# gps_tracker.net
KiCad netlist of a schematic drawn in EAGLE
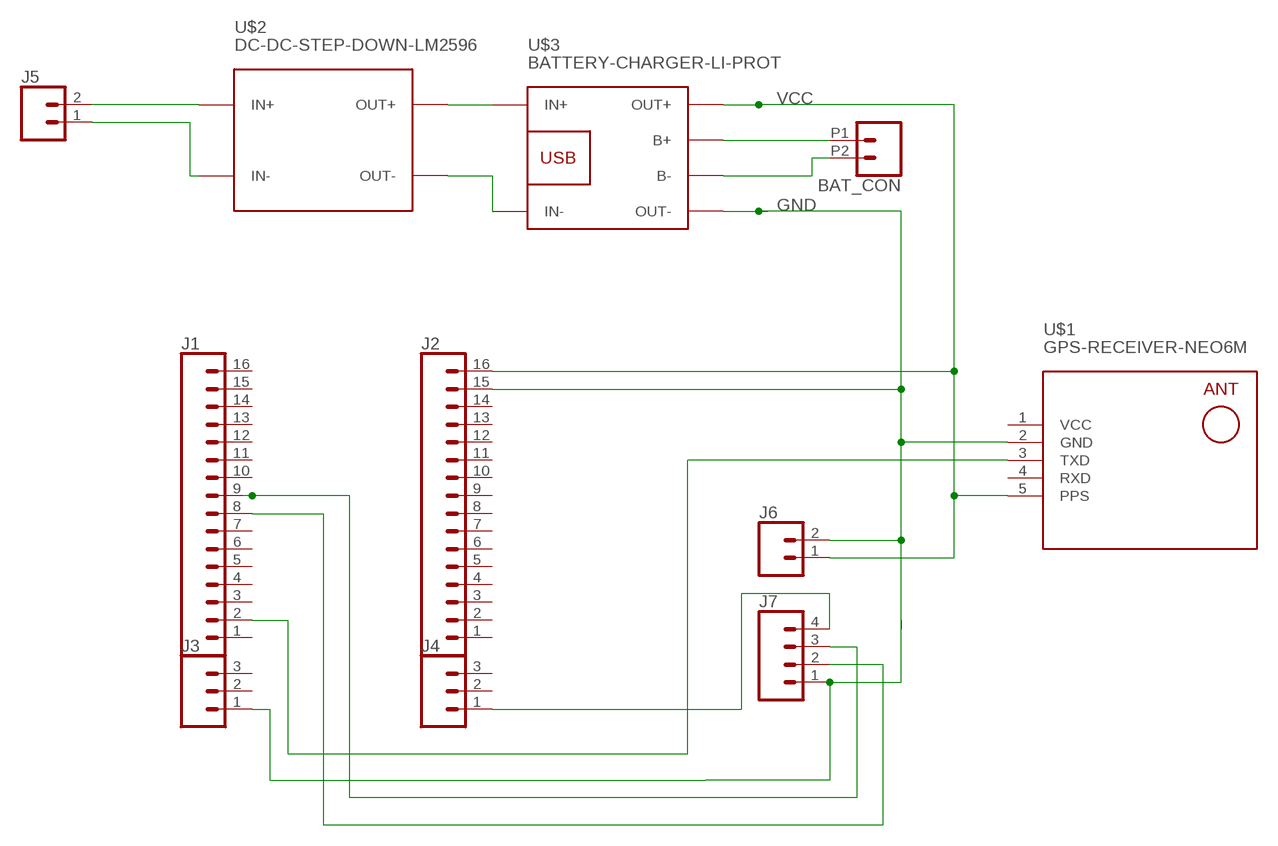
[diagram p0: schematic, sheet 1]

(export (version "E")
  (design (tool "Eeschema 10.0.6"))
  (components
    (comp (ref "BAT_CON")
      (value "CONN_022.54MM_SCREWTERM")
      (footprint "eagle-import:1X02_2.54_SCREWTERM")
      (libsource (lib "eagle-import") (part "CONN_022.54MM_SCREWTERM"))
    )
    (comp (ref "J1")
      (value "CONN_16LONGPADS")
      (footprint "eagle-import:1X16_LONGPADS")
      (fields (field (name "SPICEPREFIX") "X"))
      (libsource (lib "eagle-import") (part "CONN_16LONGPADS"))
    )
    (comp (ref "J2")
      (value "CONN_16LONGPADS")
      (footprint "eagle-import:1X16_LONGPADS")
      (fields (field (name "SPICEPREFIX") "X"))
      (libsource (lib "eagle-import") (part "CONN_16LONGPADS"))
    )
    (comp (ref "J3")
      (value "CONN_03LONGPADS")
      (footprint "eagle-import:1X03_LONGPADS")
      (fields (field (name "SPICEPREFIX") "J"))
      (libsource (lib "eagle-import") (part "CONN_03LONGPADS"))
    )
    (comp (ref "J4")
      (value "CONN_03LONGPADS")
      (footprint "eagle-import:1X03_LONGPADS")
      (fields (field (name "SPICEPREFIX") "J"))
      (libsource (lib "eagle-import") (part "CONN_03LONGPADS"))
    )
    (comp (ref "J5")
      (value "CONN_025MM")
      (footprint "eagle-import:SCREWTERMINAL-5MM-2")
      (libsource (lib "eagle-import") (part "CONN_025MM"))
    )
    (comp (ref "J6")
      (value "CONN_02PTH3")
      (footprint "eagle-import:1X02_LONGPADS")
      (libsource (lib "eagle-import") (part "CONN_02PTH3"))
    )
    (comp (ref "J7")
      (value "CONN_04LONGPADS")
      (footprint "eagle-import:1X04_LONGPADS")
      (libsource (lib "eagle-import") (part "CONN_04LONGPADS"))
    )
    (comp (ref "U$1")
      (value "GPS-RECEIVER-NEO6M")
      (footprint "eagle-import:GPS-RECEIVER-NEO6M")
      (libsource (lib "eagle-import") (part "GPS-RECEIVER-NEO6M"))
    )
    (comp (ref "U$2")
      (value "DC-DC-STEP-DOWN-LM2596")
      (footprint "eagle-import:DC-DC-STEP-DOWN-LM2596")
      (libsource (lib "eagle-import") (part "DC-DC-STEP-DOWN-LM2596"))
    )
    (comp (ref "U$3")
      (value "BATTERY-CHARGER-LI-PROT")
      (footprint "eagle-import:BATTERY-CHARGER-LI-PROT")
      (libsource (lib "eagle-import") (part "BATTERY-CHARGER-LI-PROT"))
    )
  )
  (nets
    (net (code "1") (name "/GND") (class "Default")
      (node (ref "J2") (pin "15") (pinfunction "15_15") (pintype "passive"))
      (node (ref "J3") (pin "1") (pinfunction "1_1") (pintype "passive"))
      (node (ref "J6") (pin "2") (pinfunction "2_2") (pintype "passive"))
      (node (ref "J7") (pin "1") (pinfunction "1_1") (pintype "passive"))
      (node (ref "U$1") (pin "2") (pinfunction "GND_2") (pintype "bidirectional"))
      (node (ref "U$3") (pin "OUT-") (pinfunction "OUT-_OUT-") (pintype "bidirectional"))
    )
    (net (code "2") (name "/RXD") (class "Default")
      (node (ref "U$1") (pin "4") (pinfunction "RXD_4") (pintype "power_in"))
    )
    (net (code "3") (name "/VCC") (class "Default")
      (node (ref "J2") (pin "16") (pinfunction "16_16") (pintype "passive"))
      (node (ref "J6") (pin "1") (pinfunction "1_1") (pintype "passive"))
      (node (ref "U$1") (pin "5") (pinfunction "PPS_5") (pintype "power_in"))
      (node (ref "U$3") (pin "OUT+") (pinfunction "OUT+_OUT+") (pintype "bidirectional"))
    )
    (net (code "4") (name "Net-(BAT_CON-1)") (class "Default")
      (node (ref "BAT_CON") (pin "P1") (pinfunction "1_P1") (pintype "passive"))
      (node (ref "U$3") (pin "B+") (pinfunction "B+_B+") (pintype "bidirectional"))
    )
    (net (code "5") (name "Net-(BAT_CON-2)") (class "Default")
      (node (ref "BAT_CON") (pin "P2") (pinfunction "2_P2") (pintype "passive"))
      (node (ref "U$3") (pin "B-") (pinfunction "B-_B-") (pintype "bidirectional"))
    )
    (net (code "6") (name "Net-(J1-Pad8)") (class "Default")
      (node (ref "J1") (pin "8") (pinfunction "8_8") (pintype "passive"))
      (node (ref "J7") (pin "2") (pinfunction "2_2") (pintype "passive"))
    )
    (net (code "7") (name "Net-(J1-Pad9)") (class "Default")
      (node (ref "J1") (pin "9") (pinfunction "9_9") (pintype "passive"))
      (node (ref "J7") (pin "3") (pinfunction "3_3") (pintype "passive"))
    )
    (net (code "8") (name "Net-(J4-Pad1)") (class "Default")
      (node (ref "J4") (pin "1") (pinfunction "1_1") (pintype "passive"))
      (node (ref "J7") (pin "4") (pinfunction "4_4") (pintype "passive"))
    )
    (net (code "9") (name "Net-(J5-Pad1)") (class "Default")
      (node (ref "J5") (pin "1") (pinfunction "1_1") (pintype "passive"))
      (node (ref "U$2") (pin "IN-") (pinfunction "IN-_IN-") (pintype "bidirectional"))
    )
    (net (code "10") (name "Net-(J5-Pad2)") (class "Default")
      (node (ref "J5") (pin "2") (pinfunction "2_2") (pintype "passive"))
      (node (ref "U$2") (pin "IN+") (pinfunction "IN+_IN+") (pintype "bidirectional"))
    )
    (net (code "11") (name "Net-(U$1-TXD)") (class "Default")
      (node (ref "J1") (pin "2") (pinfunction "2_2") (pintype "passive"))
      (node (ref "U$1") (pin "3") (pinfunction "TXD_3") (pintype "bidirectional"))
    )
    (net (code "12") (name "Net-(U$2-PadOUT+)") (class "Default")
      (node (ref "U$2") (pin "OUT+") (pinfunction "OUT+_OUT+") (pintype "bidirectional"))
      (node (ref "U$3") (pin "IN+") (pinfunction "IN+_IN+") (pintype "bidirectional"))
    )
    (net (code "13") (name "Net-(U$2-PadOUT-)") (class "Default")
      (node (ref "U$2") (pin "OUT-") (pinfunction "OUT-_OUT-") (pintype "bidirectional"))
      (node (ref "U$3") (pin "IN-") (pinfunction "IN-_IN-") (pintype "bidirectional"))
    )
    (net (code "14") (name "unconnected-(J1-Pad1)") (class "Default")
      (node (ref "J1") (pin "1") (pinfunction "1_1") (pintype "passive"))
    )
    (net (code "15") (name "unconnected-(J1-Pad3)") (class "Default")
      (node (ref "J1") (pin "3") (pinfunction "3_3") (pintype "passive"))
    )
    (net (code "16") (name "unconnected-(J1-Pad4)") (class "Default")
      (node (ref "J1") (pin "4") (pinfunction "4_4") (pintype "passive"))
    )
    (net (code "17") (name "unconnected-(J1-Pad5)") (class "Default")
      (node (ref "J1") (pin "5") (pinfunction "5_5") (pintype "passive"))
    )
    (net (code "18") (name "unconnected-(J1-Pad6)") (class "Default")
      (node (ref "J1") (pin "6") (pinfunction "6_6") (pintype "passive"))
    )
    (net (code "19") (name "unconnected-(J1-Pad7)") (class "Default")
      (node (ref "J1") (pin "7") (pinfunction "7_7") (pintype "passive"))
    )
    (net (code "20") (name "unconnected-(J1-Pad10)") (class "Default")
      (node (ref "J1") (pin "10") (pinfunction "10_10") (pintype "passive"))
    )
    (net (code "21") (name "unconnected-(J1-Pad11)") (class "Default")
      (node (ref "J1") (pin "11") (pinfunction "11_11") (pintype "passive"))
    )
    (net (code "22") (name "unconnected-(J1-Pad12)") (class "Default")
      (node (ref "J1") (pin "12") (pinfunction "12_12") (pintype "passive"))
    )
    (net (code "23") (name "unconnected-(J1-Pad13)") (class "Default")
      (node (ref "J1") (pin "13") (pinfunction "13_13") (pintype "passive"))
    )
    (net (code "24") (name "unconnected-(J1-Pad14)") (class "Default")
      (node (ref "J1") (pin "14") (pinfunction "14_14") (pintype "passive"))
    )
    (net (code "25") (name "unconnected-(J1-Pad15)") (class "Default")
      (node (ref "J1") (pin "15") (pinfunction "15_15") (pintype "passive"))
    )
    (net (code "26") (name "unconnected-(J1-Pad16)") (class "Default")
      (node (ref "J1") (pin "16") (pinfunction "16_16") (pintype "passive"))
    )
    (net (code "27") (name "unconnected-(J2-Pad1)") (class "Default")
      (node (ref "J2") (pin "1") (pinfunction "1_1") (pintype "passive"))
    )
    (net (code "28") (name "unconnected-(J2-Pad2)") (class "Default")
      (node (ref "J2") (pin "2") (pinfunction "2_2") (pintype "passive"))
    )
    (net (code "29") (name "unconnected-(J2-Pad3)") (class "Default")
      (node (ref "J2") (pin "3") (pinfunction "3_3") (pintype "passive"))
    )
    (net (code "30") (name "unconnected-(J2-Pad4)") (class "Default")
      (node (ref "J2") (pin "4") (pinfunction "4_4") (pintype "passive"))
    )
    (net (code "31") (name "unconnected-(J2-Pad5)") (class "Default")
      (node (ref "J2") (pin "5") (pinfunction "5_5") (pintype "passive"))
    )
    (net (code "32") (name "unconnected-(J2-Pad6)") (class "Default")
      (node (ref "J2") (pin "6") (pinfunction "6_6") (pintype "passive"))
    )
    (net (code "33") (name "unconnected-(J2-Pad7)") (class "Default")
      (node (ref "J2") (pin "7") (pinfunction "7_7") (pintype "passive"))
    )
    (net (code "34") (name "unconnected-(J2-Pad8)") (class "Default")
      (node (ref "J2") (pin "8") (pinfunction "8_8") (pintype "passive"))
    )
    (net (code "35") (name "unconnected-(J2-Pad9)") (class "Default")
      (node (ref "J2") (pin "9") (pinfunction "9_9") (pintype "passive"))
    )
    (net (code "36") (name "unconnected-(J2-Pad10)") (class "Default")
      (node (ref "J2") (pin "10") (pinfunction "10_10") (pintype "passive"))
    )
    (net (code "37") (name "unconnected-(J2-Pad11)") (class "Default")
      (node (ref "J2") (pin "11") (pinfunction "11_11") (pintype "passive"))
    )
    (net (code "38") (name "unconnected-(J2-Pad12)") (class "Default")
      (node (ref "J2") (pin "12") (pinfunction "12_12") (pintype "passive"))
    )
    (net (code "39") (name "unconnected-(J2-Pad13)") (class "Default")
      (node (ref "J2") (pin "13") (pinfunction "13_13") (pintype "passive"))
    )
    (net (code "40") (name "unconnected-(J2-Pad14)") (class "Default")
      (node (ref "J2") (pin "14") (pinfunction "14_14") (pintype "passive"))
    )
    (net (code "41") (name "unconnected-(J3-Pad2)") (class "Default")
      (node (ref "J3") (pin "2") (pinfunction "2_2") (pintype "passive"))
    )
    (net (code "42") (name "unconnected-(J3-Pad3)") (class "Default")
      (node (ref "J3") (pin "3") (pinfunction "3_3") (pintype "passive"))
    )
    (net (code "43") (name "unconnected-(J4-Pad2)") (class "Default")
      (node (ref "J4") (pin "2") (pinfunction "2_2") (pintype "passive"))
    )
    (net (code "44") (name "unconnected-(J4-Pad3)") (class "Default")
      (node (ref "J4") (pin "3") (pinfunction "3_3") (pintype "passive"))
    )
    (net (code "45") (name "unconnected-(U$1-VCC-Pad1)") (class "Default")
      (node (ref "U$1") (pin "1") (pinfunction "VCC_1") (pintype "bidirectional"))
    )
  )
)
